# GettingStarted.net
KiCad netlist of a schematic drawn in EAGLE
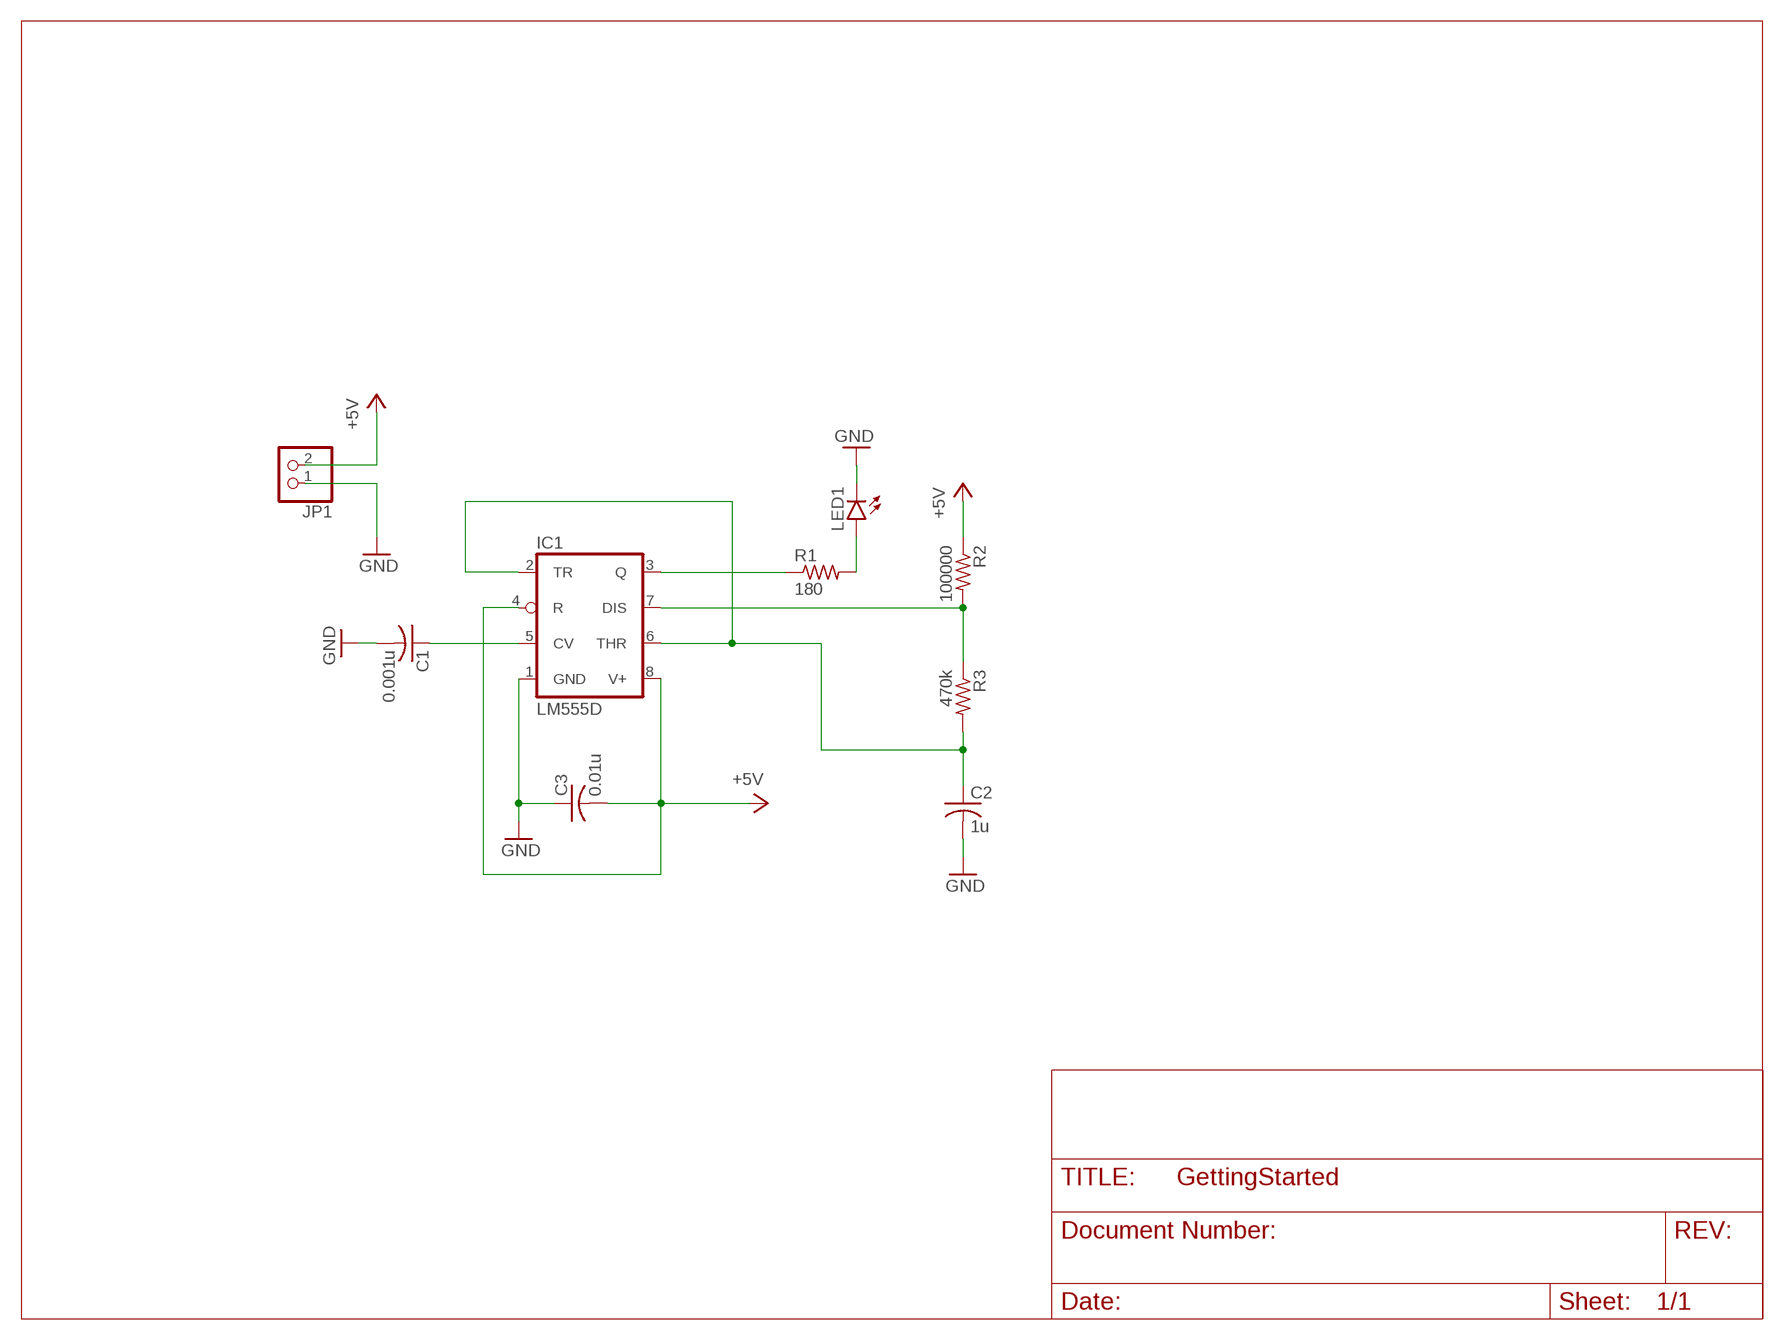
[diagram p0: schematic, sheet 1]

(export (version "E")
  (design (tool "Eeschema 10.0.6"))
  (components
    (comp (ref "C1")
      (value "0.001u")
      (footprint "eagle-import:C0805")
      (libsource (lib "eagle-import") (part "C-USC0805"))
    )
    (comp (ref "C2")
      (value "1u")
      (footprint "eagle-import:C0805")
      (libsource (lib "eagle-import") (part "C-USC0805"))
    )
    (comp (ref "C3")
      (value "0.01u")
      (footprint "eagle-import:C0805")
      (libsource (lib "eagle-import") (part "C-USC0805"))
    )
    (comp (ref "IC1")
      (value "LM555D")
      (footprint "eagle-import:SO08")
      (libsource (lib "eagle-import") (part "555DLM"))
    )
    (comp (ref "JP1")
      (value "PINHD-1X2")
      (footprint "eagle-import:1X02")
      (libsource (lib "eagle-import") (part "PINHD-1X2"))
    )
    (comp (ref "LED1")
      (value "LED5MM")
      (footprint "eagle-import:LED5MM")
      (libsource (lib "eagle-import") (part "LED5MM"))
    )
    (comp (ref "R1")
      (value "180")
      (footprint "eagle-import:R0805")
      (libsource (lib "eagle-import") (part "R-US_R0805"))
    )
    (comp (ref "R2")
      (value "100000")
      (footprint "eagle-import:R0805")
      (libsource (lib "eagle-import") (part "R-US_R0805"))
    )
    (comp (ref "R3")
      (value "470k")
      (footprint "eagle-import:R0805")
      (libsource (lib "eagle-import") (part "R-US_R0805"))
    )
  )
  (nets
    (net (code "1") (name "+5V") (class "Default")
      (node (ref "C3") (pin "2") (pinfunction "2_2") (pintype "passive"))
      (node (ref "IC1") (pin "4") (pinfunction "R_4") (pintype "input"))
      (node (ref "IC1") (pin "8") (pinfunction "V+_8") (pintype "power_in"))
      (node (ref "JP1") (pin "2") (pinfunction "2_2") (pintype "passive"))
      (node (ref "R2") (pin "1") (pinfunction "1_1") (pintype "passive"))
    )
    (net (code "2") (name "GND") (class "Default")
      (node (ref "C1") (pin "2") (pinfunction "2_2") (pintype "passive"))
      (node (ref "C2") (pin "2") (pinfunction "2_2") (pintype "passive"))
      (node (ref "C3") (pin "1") (pinfunction "1_1") (pintype "passive"))
      (node (ref "IC1") (pin "1") (pinfunction "GND_1") (pintype "power_in"))
      (node (ref "JP1") (pin "1") (pinfunction "1_1") (pintype "passive"))
      (node (ref "LED1") (pin "K") (pinfunction "C_K") (pintype "passive"))
    )
    (net (code "3") (name "Net-(IC1-CV)") (class "Default")
      (node (ref "C1") (pin "1") (pinfunction "1_1") (pintype "passive"))
      (node (ref "IC1") (pin "5") (pinfunction "CV_5") (pintype "input"))
    )
    (net (code "4") (name "Net-(IC1-DIS)") (class "Default")
      (node (ref "IC1") (pin "7") (pinfunction "DIS_7") (pintype "input"))
      (node (ref "R2") (pin "2") (pinfunction "2_2") (pintype "passive"))
      (node (ref "R3") (pin "1") (pinfunction "1_1") (pintype "passive"))
    )
    (net (code "5") (name "Net-(IC1-Q)") (class "Default")
      (node (ref "IC1") (pin "3") (pinfunction "Q_3") (pintype "output"))
      (node (ref "R1") (pin "1") (pinfunction "1_1") (pintype "passive"))
    )
    (net (code "6") (name "Net-(IC1-THR)") (class "Default")
      (node (ref "C2") (pin "1") (pinfunction "1_1") (pintype "passive"))
      (node (ref "IC1") (pin "2") (pinfunction "TR_2") (pintype "input"))
      (node (ref "IC1") (pin "6") (pinfunction "THR_6") (pintype "input"))
      (node (ref "R3") (pin "2") (pinfunction "2_2") (pintype "passive"))
    )
    (net (code "7") (name "Net-(LED1-PadA)") (class "Default")
      (node (ref "LED1") (pin "A") (pinfunction "A_A") (pintype "passive"))
      (node (ref "R1") (pin "2") (pinfunction "2_2") (pintype "passive"))
    )
  )
)
